# 07_MIPI_DSI.net
KiCad netlist of a schematic drawn in Altium Designer
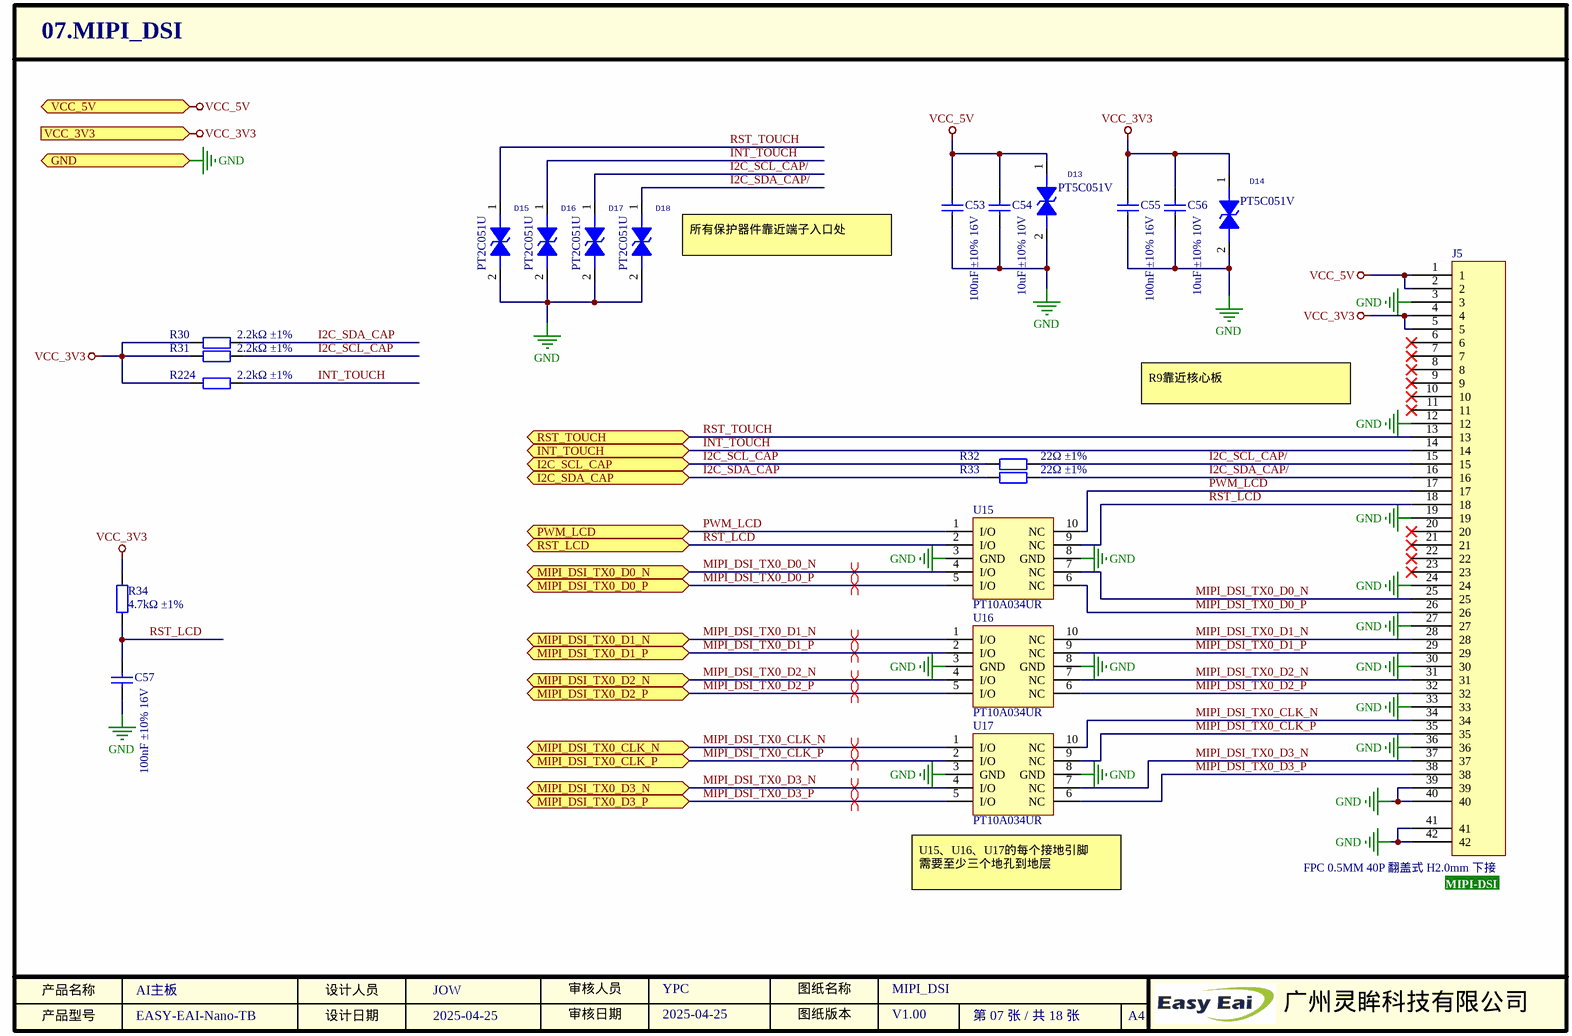
[diagram p0: 07.MIPI_DSI.SchDoc]

(export (version "E")
  (design (tool "Eeschema 10.0.6"))
  (components
    (comp (ref "C53")
      (value "CL05B104KO5NNNC")
      (footprint "0402_C")
      (description "SPZL000259")
      (fields (field (name "描述") "100nF ±10% 16V"))
      (libsource (lib "CAP_EASY-EAI") (part "0402 100nF ±10% 16V"))
    )
    (comp (ref "C54")
      (value "CL10A106KP8NNNC")
      (footprint "0603_C")
      (description "SPZL000260")
      (fields (field (name "描述") "10uF ±10% 10V"))
      (libsource (lib "CAP_EASY-EAI") (part "0603 10uF ±10% 10V"))
    )
    (comp (ref "C55")
      (value "CL05B104KO5NNNC")
      (footprint "0402_C")
      (description "SPZL000259")
      (fields (field (name "描述") "100nF ±10% 16V"))
      (libsource (lib "CAP_EASY-EAI") (part "0402 100nF ±10% 16V"))
    )
    (comp (ref "C56")
      (value "CL10A106KP8NNNC")
      (footprint "0603_C")
      (description "SPZL000260")
      (fields (field (name "描述") "10uF ±10% 10V"))
      (libsource (lib "CAP_EASY-EAI") (part "0603 10uF ±10% 10V"))
    )
    (comp (ref "C57")
      (value "CL05B104KO5NNNC")
      (footprint "0402_C")
      (description "SPZL000259")
      (fields (field (name "描述") "100nF ±10% 16V"))
      (libsource (lib "CAP_EASY-EAI") (part "0402 100nF ±10% 16V"))
    )
    (comp (ref "D13")
      (value "PT5C051V")
      (footprint "SOD-523")
      (description "SPZL001155")
      (fields (field (name "型号") "PT5C051V"))
      (libsource (lib "ESD_EASY-EAI") (part "PT5C051V"))
    )
    (comp (ref "D14")
      (value "PT5C051V")
      (footprint "SOD-523")
      (description "SPZL001155")
      (fields (field (name "型号") "PT5C051V"))
      (libsource (lib "ESD_EASY-EAI") (part "PT5C051V"))
    )
    (comp (ref "D15")
      (value "PT2C051U")
      (footprint "DFN1006")
      (description "SPZL001147")
      (fields (field (name "型号") "PT2C051U"))
      (libsource (lib "ESD_EASY-EAI") (part "PT2C051U"))
    )
    (comp (ref "D16")
      (value "PT2C051U")
      (footprint "DFN1006")
      (description "SPZL001147")
      (fields (field (name "型号") "PT2C051U"))
      (libsource (lib "ESD_EASY-EAI") (part "PT2C051U"))
    )
    (comp (ref "D17")
      (value "PT2C051U")
      (footprint "DFN1006")
      (description "SPZL001147")
      (fields (field (name "型号") "PT2C051U"))
      (libsource (lib "ESD_EASY-EAI") (part "PT2C051U"))
    )
    (comp (ref "D18")
      (value "PT2C051U")
      (footprint "DFN1006")
      (description "SPZL001147")
      (fields (field (name "型号") "PT2C051U"))
      (libsource (lib "ESD_EASY-EAI") (part "PT2C051U"))
    )
    (comp (ref "J5")
      (value "AFC01-S40FCA-00")
      (footprint "FFC0.5-40P")
      (description "SPZL000107")
      (fields (field (name "描述") "FPC 0.5MM 40P 翻盖式 H2.0mm 下接"))
      (libsource (lib "FPC_lexing") (part "FPC 0.5MM 40P 翻盖式 H2.0mm 下接"))
    )
    (comp (ref "R30")
      (value "AC0402FR-072K2L")
      (footprint "0402_R")
      (description "SPZL000307")
      (fields (field (name "描述") "2.2kΩ ±1%"))
      (libsource (lib "RES_EASY-EAI") (part "0402 2.2kΩ ±1%"))
    )
    (comp (ref "R31")
      (value "AC0402FR-072K2L")
      (footprint "0402_R")
      (description "SPZL000307")
      (fields (field (name "描述") "2.2kΩ ±1%"))
      (libsource (lib "RES_EASY-EAI") (part "0402 2.2kΩ ±1%"))
    )
    (comp (ref "R32")
      (value "0402WGF220JTCE")
      (footprint "0402_R")
      (description "SPZL000279")
      (fields (field (name "描述") "22Ω ±1%"))
      (libsource (lib "RES_EASY-EAI") (part "0402 22Ω ±1%"))
    )
    (comp (ref "R33")
      (value "0402WGF220JTCE")
      (footprint "0402_R")
      (description "SPZL000279")
      (fields (field (name "描述") "22Ω ±1%"))
      (libsource (lib "RES_EASY-EAI") (part "0402 22Ω ±1%"))
    )
    (comp (ref "R34")
      (value "0402WGF4701TCE")
      (footprint "0402_R")
      (description "SPZL000280")
      (fields (field (name "描述") "4.7kΩ ±1%"))
      (libsource (lib "RES_EASY-EAI") (part "0402 4.7kΩ ±1%"))
    )
    (comp (ref "R224")
      (value "AC0402FR-072K2L")
      (footprint "0402_R")
      (description "SPZL000307")
      (fields (field (name "描述") "2.2kΩ ±1%"))
      (libsource (lib "RES_EASY-EAI") (part "0402 2.2kΩ ±1%"))
    )
    (comp (ref "U15")
      (value "PT10A034UR")
      (footprint "DFN2510")
      (description "SPZL001146")
      (fields (field (name "型号") "PT10A034UR"))
      (libsource (lib "ESD_EASY-EAI") (part "PT10A034UR"))
    )
    (comp (ref "U16")
      (value "PT10A034UR")
      (footprint "DFN2510")
      (description "SPZL001146")
      (fields (field (name "型号") "PT10A034UR"))
      (libsource (lib "ESD_EASY-EAI") (part "PT10A034UR"))
    )
    (comp (ref "U17")
      (value "PT10A034UR")
      (footprint "DFN2510")
      (description "SPZL001146")
      (fields (field (name "型号") "PT10A034UR"))
      (libsource (lib "ESD_EASY-EAI") (part "PT10A034UR"))
    )
  )
  (nets
    (net (code "1") (name "/I2C_SCL_CAP") (class "Default")
      (node (ref "R31") (pin "2") (pinfunction "2_2") (pintype "passive"))
      (node (ref "R32") (pin "1") (pinfunction "1_1") (pintype "passive"))
    )
    (net (code "2") (name "/I2C_SCL_CAP{slash}") (class "Default")
      (node (ref "D17") (pin "1") (pinfunction "1_1") (pintype "passive"))
      (node (ref "J5") (pin "15") (pinfunction "15_15") (pintype "passive"))
      (node (ref "R32") (pin "2") (pinfunction "2_2") (pintype "passive"))
    )
    (net (code "3") (name "/I2C_SDA_CAP") (class "Default")
      (node (ref "R30") (pin "2") (pinfunction "2_2") (pintype "passive"))
      (node (ref "R33") (pin "1") (pinfunction "1_1") (pintype "passive"))
    )
    (net (code "4") (name "/I2C_SDA_CAP{slash}") (class "Default")
      (node (ref "D18") (pin "1") (pinfunction "1_1") (pintype "passive"))
      (node (ref "J5") (pin "16") (pinfunction "16_16") (pintype "passive"))
      (node (ref "R33") (pin "2") (pinfunction "2_2") (pintype "passive"))
    )
    (net (code "5") (name "/INT_TOUCH") (class "Default")
      (node (ref "D16") (pin "1") (pinfunction "1_1") (pintype "passive"))
      (node (ref "J5") (pin "14") (pinfunction "14_14") (pintype "passive"))
      (node (ref "R224") (pin "2") (pinfunction "2_2") (pintype "passive"))
    )
    (net (code "6") (name "/MIPI_DSI_TX0_CLK_N") (class "Default")
      (node (ref "J5") (pin "34") (pinfunction "34_34") (pintype "passive"))
      (node (ref "U17") (pin "1") (pinfunction "I/O_1") (pintype "passive"))
      (node (ref "U17") (pin "10") (pinfunction "NC_10") (pintype "passive"))
    )
    (net (code "7") (name "/MIPI_DSI_TX0_CLK_P") (class "Default")
      (node (ref "J5") (pin "35") (pinfunction "35_35") (pintype "passive"))
      (node (ref "U17") (pin "2") (pinfunction "I/O_2") (pintype "passive"))
      (node (ref "U17") (pin "9") (pinfunction "NC_9") (pintype "passive"))
    )
    (net (code "8") (name "/MIPI_DSI_TX0_D0_N") (class "Default")
      (node (ref "J5") (pin "25") (pinfunction "25_25") (pintype "passive"))
      (node (ref "U15") (pin "4") (pinfunction "I/O_4") (pintype "passive"))
      (node (ref "U15") (pin "7") (pinfunction "NC_7") (pintype "passive"))
    )
    (net (code "9") (name "/MIPI_DSI_TX0_D0_P") (class "Default")
      (node (ref "J5") (pin "26") (pinfunction "26_26") (pintype "passive"))
      (node (ref "U15") (pin "5") (pinfunction "I/O_5") (pintype "passive"))
      (node (ref "U15") (pin "6") (pinfunction "NC_6") (pintype "passive"))
    )
    (net (code "10") (name "/MIPI_DSI_TX0_D1_N") (class "Default")
      (node (ref "J5") (pin "28") (pinfunction "28_28") (pintype "passive"))
      (node (ref "U16") (pin "1") (pinfunction "I/O_1") (pintype "passive"))
      (node (ref "U16") (pin "10") (pinfunction "NC_10") (pintype "passive"))
    )
    (net (code "11") (name "/MIPI_DSI_TX0_D1_P") (class "Default")
      (node (ref "J5") (pin "29") (pinfunction "29_29") (pintype "passive"))
      (node (ref "U16") (pin "2") (pinfunction "I/O_2") (pintype "passive"))
      (node (ref "U16") (pin "9") (pinfunction "NC_9") (pintype "passive"))
    )
    (net (code "12") (name "/MIPI_DSI_TX0_D2_N") (class "Default")
      (node (ref "J5") (pin "31") (pinfunction "31_31") (pintype "passive"))
      (node (ref "U16") (pin "4") (pinfunction "I/O_4") (pintype "passive"))
      (node (ref "U16") (pin "7") (pinfunction "NC_7") (pintype "passive"))
    )
    (net (code "13") (name "/MIPI_DSI_TX0_D2_P") (class "Default")
      (node (ref "J5") (pin "32") (pinfunction "32_32") (pintype "passive"))
      (node (ref "U16") (pin "5") (pinfunction "I/O_5") (pintype "passive"))
      (node (ref "U16") (pin "6") (pinfunction "NC_6") (pintype "passive"))
    )
    (net (code "14") (name "/MIPI_DSI_TX0_D3_N") (class "Default")
      (node (ref "J5") (pin "37") (pinfunction "37_37") (pintype "passive"))
      (node (ref "U17") (pin "4") (pinfunction "I/O_4") (pintype "passive"))
      (node (ref "U17") (pin "7") (pinfunction "NC_7") (pintype "passive"))
    )
    (net (code "15") (name "/MIPI_DSI_TX0_D3_P") (class "Default")
      (node (ref "J5") (pin "38") (pinfunction "38_38") (pintype "passive"))
      (node (ref "U17") (pin "5") (pinfunction "I/O_5") (pintype "passive"))
      (node (ref "U17") (pin "6") (pinfunction "NC_6") (pintype "passive"))
    )
    (net (code "16") (name "/PWM_LCD") (class "Default")
      (node (ref "J5") (pin "17") (pinfunction "17_17") (pintype "passive"))
      (node (ref "U15") (pin "1") (pinfunction "I/O_1") (pintype "passive"))
      (node (ref "U15") (pin "10") (pinfunction "NC_10") (pintype "passive"))
    )
    (net (code "17") (name "/RST_LCD") (class "Default")
      (node (ref "C57") (pin "2") (pinfunction "2_2") (pintype "passive"))
      (node (ref "J5") (pin "18") (pinfunction "18_18") (pintype "passive"))
      (node (ref "R34") (pin "1") (pinfunction "1_1") (pintype "passive"))
      (node (ref "U15") (pin "2") (pinfunction "I/O_2") (pintype "passive"))
      (node (ref "U15") (pin "9") (pinfunction "NC_9") (pintype "passive"))
    )
    (net (code "18") (name "/RST_TOUCH") (class "Default")
      (node (ref "D15") (pin "1") (pinfunction "1_1") (pintype "passive"))
      (node (ref "J5") (pin "13") (pinfunction "13_13") (pintype "passive"))
    )
    (net (code "19") (name "GND") (class "Default")
      (node (ref "C53") (pin "1") (pinfunction "1_1") (pintype "passive"))
      (node (ref "C54") (pin "1") (pinfunction "1_1") (pintype "passive"))
      (node (ref "C55") (pin "1") (pinfunction "1_1") (pintype "passive"))
      (node (ref "C56") (pin "1") (pinfunction "1_1") (pintype "passive"))
      (node (ref "C57") (pin "1") (pinfunction "1_1") (pintype "passive"))
      (node (ref "D13") (pin "2") (pinfunction "2_2") (pintype "passive"))
      (node (ref "D14") (pin "2") (pinfunction "2_2") (pintype "passive"))
      (node (ref "D15") (pin "2") (pinfunction "2_2") (pintype "passive"))
      (node (ref "D16") (pin "2") (pinfunction "2_2") (pintype "passive"))
      (node (ref "D17") (pin "2") (pinfunction "2_2") (pintype "passive"))
      (node (ref "D18") (pin "2") (pinfunction "2_2") (pintype "passive"))
      (node (ref "J5") (pin "12") (pinfunction "12_12") (pintype "passive"))
      (node (ref "J5") (pin "19") (pinfunction "19_19") (pintype "passive"))
      (node (ref "J5") (pin "24") (pinfunction "24_24") (pintype "passive"))
      (node (ref "J5") (pin "27") (pinfunction "27_27") (pintype "passive"))
      (node (ref "J5") (pin "3") (pinfunction "3_3") (pintype "passive"))
      (node (ref "J5") (pin "30") (pinfunction "30_30") (pintype "passive"))
      (node (ref "J5") (pin "33") (pinfunction "33_33") (pintype "passive"))
      (node (ref "J5") (pin "36") (pinfunction "36_36") (pintype "passive"))
      (node (ref "J5") (pin "39") (pinfunction "39_39") (pintype "passive"))
      (node (ref "J5") (pin "40") (pinfunction "40_40") (pintype "passive"))
      (node (ref "J5") (pin "41") (pinfunction "41_41") (pintype "passive"))
      (node (ref "J5") (pin "42") (pinfunction "42_42") (pintype "passive"))
      (node (ref "U15") (pin "3") (pinfunction "GND_3") (pintype "passive"))
      (node (ref "U15") (pin "8") (pinfunction "GND_8") (pintype "passive"))
      (node (ref "U16") (pin "3") (pinfunction "GND_3") (pintype "passive"))
      (node (ref "U16") (pin "8") (pinfunction "GND_8") (pintype "passive"))
      (node (ref "U17") (pin "3") (pinfunction "GND_3") (pintype "passive"))
      (node (ref "U17") (pin "8") (pinfunction "GND_8") (pintype "passive"))
    )
    (net (code "20") (name "VCC_3V3") (class "Default")
      (node (ref "C55") (pin "2") (pinfunction "2_2") (pintype "passive"))
      (node (ref "C56") (pin "2") (pinfunction "2_2") (pintype "passive"))
      (node (ref "D14") (pin "1") (pinfunction "1_1") (pintype "passive"))
      (node (ref "J5") (pin "4") (pinfunction "4_4") (pintype "passive"))
      (node (ref "J5") (pin "5") (pinfunction "5_5") (pintype "passive"))
      (node (ref "R224") (pin "1") (pinfunction "1_1") (pintype "passive"))
      (node (ref "R30") (pin "1") (pinfunction "1_1") (pintype "passive"))
      (node (ref "R31") (pin "1") (pinfunction "1_1") (pintype "passive"))
      (node (ref "R34") (pin "2") (pinfunction "2_2") (pintype "passive"))
    )
    (net (code "21") (name "VCC_5V") (class "Default")
      (node (ref "C53") (pin "2") (pinfunction "2_2") (pintype "passive"))
      (node (ref "C54") (pin "2") (pinfunction "2_2") (pintype "passive"))
      (node (ref "D13") (pin "1") (pinfunction "1_1") (pintype "passive"))
      (node (ref "J5") (pin "1") (pinfunction "1_1") (pintype "passive"))
      (node (ref "J5") (pin "2") (pinfunction "2_2") (pintype "passive"))
    )
    (net (code "22") (name "unconnected-(J5-Pad6)") (class "Default")
      (node (ref "J5") (pin "6") (pinfunction "6_6") (pintype "passive+no_connect"))
    )
    (net (code "23") (name "unconnected-(J5-Pad7)") (class "Default")
      (node (ref "J5") (pin "7") (pinfunction "7_7") (pintype "passive+no_connect"))
    )
    (net (code "24") (name "unconnected-(J5-Pad8)") (class "Default")
      (node (ref "J5") (pin "8") (pinfunction "8_8") (pintype "passive+no_connect"))
    )
    (net (code "25") (name "unconnected-(J5-Pad9)") (class "Default")
      (node (ref "J5") (pin "9") (pinfunction "9_9") (pintype "passive+no_connect"))
    )
    (net (code "26") (name "unconnected-(J5-Pad10)") (class "Default")
      (node (ref "J5") (pin "10") (pinfunction "10_10") (pintype "passive+no_connect"))
    )
    (net (code "27") (name "unconnected-(J5-Pad11)") (class "Default")
      (node (ref "J5") (pin "11") (pinfunction "11_11") (pintype "passive+no_connect"))
    )
    (net (code "28") (name "unconnected-(J5-Pad20)") (class "Default")
      (node (ref "J5") (pin "20") (pinfunction "20_20") (pintype "passive+no_connect"))
    )
    (net (code "29") (name "unconnected-(J5-Pad21)") (class "Default")
      (node (ref "J5") (pin "21") (pinfunction "21_21") (pintype "passive+no_connect"))
    )
    (net (code "30") (name "unconnected-(J5-Pad22)") (class "Default")
      (node (ref "J5") (pin "22") (pinfunction "22_22") (pintype "passive+no_connect"))
    )
    (net (code "31") (name "unconnected-(J5-Pad23)") (class "Default")
      (node (ref "J5") (pin "23") (pinfunction "23_23") (pintype "passive+no_connect"))
    )
  )
)
